# Boost_converter.net
KiCad netlist of a schematic drawn in Altium Designer
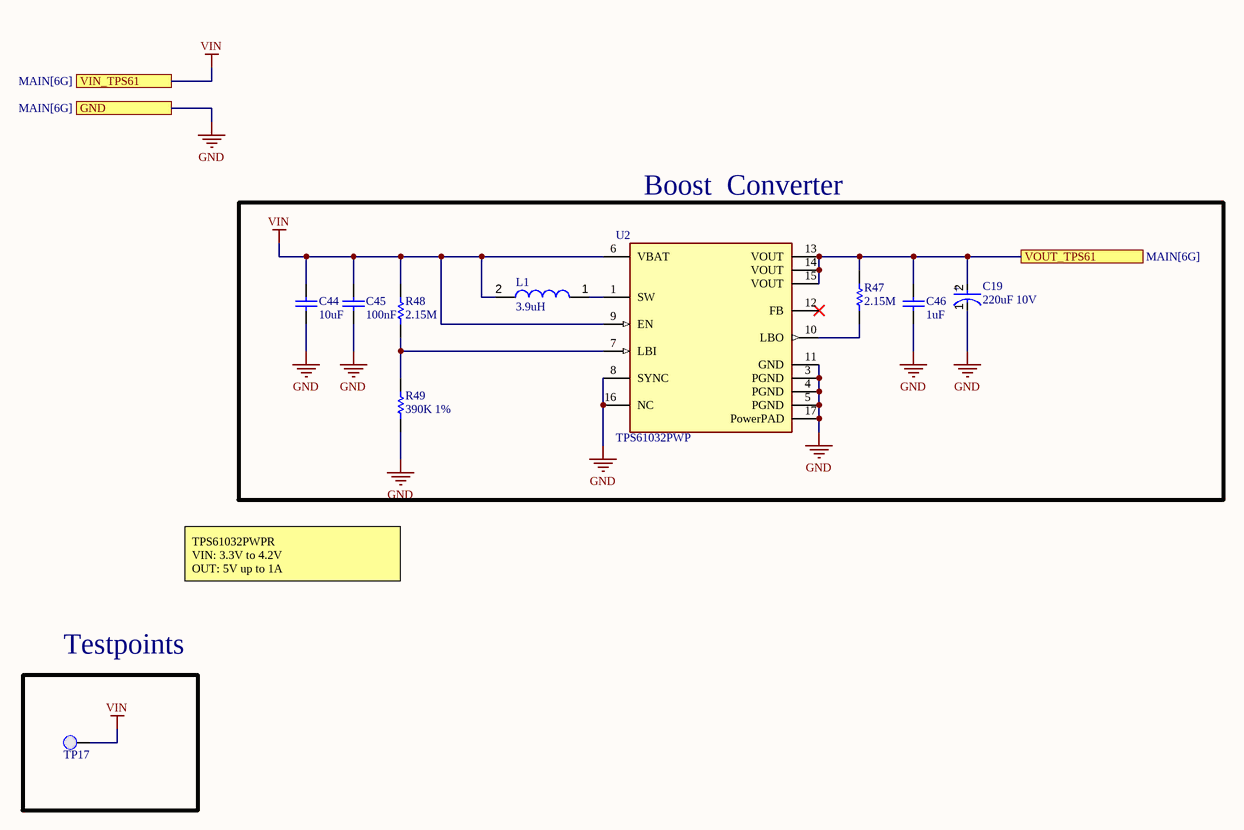
[diagram p0: Boost converter.SchDoc]

(export (version "E")
  (design (tool "Eeschema 10.0.6"))
  (components
    (comp (ref "C19")
      (value "220uF 10V")
      (footprint "FP-T495D227K010ATE100-MFG")
      (description "CAP TANT 220UF 10% 10V 2917, T495D227K010ATE100")
      (fields (field (name "TOLERANCE") "10%") (field (name "VOLTAGE") "10V"))
      (libsource (lib "Altium Content Vault") (part "203bc49f2ac43e59fd269a8c329ed05"))
    )
    (comp (ref "C44")
      (value "10uF")
      (footprint "CAPC2012X127N")
      (description "Boost Cin, Buck Cin-Cap Ceramic 10uF 16V X7R 20% SMD 0805 125°C Blister T/R")
      (fields (field (name "TOLERANCE") "20%") (field (name "MANUFACTURER") "Murata"))
      (libsource (lib "Schlib1") (part "CMP-06035-062410-1"))
    )
    (comp (ref "C45")
      (value "100nF")
      (footprint "CAPC1005X55X25LL05T10")
      (description "Boost Cinx, Cap 100NF 16V 0402 SMD 10% X7R")
      (fields
        (field (name "MANUFACTURER") "Murata")
        (field (name "MANUFACTURER PART NUMBER") "GRM155R71A104KA01D")
      )
      (libsource (lib "Schlib1") (part "CMP-2000-06331-1"))
    )
    (comp (ref "C46")
      (value "1uF")
      (footprint "CAPC1608X90")
      (description "Boost Coutx, Cap Ceramic 1uF 16V X7R 5% SMD 0603 125°C Paper T/R")
      (fields (field (name "MF") "{'manufacturer': u'KEMET'}") (field (name "MP") "C0603C105K8PACTU"))
      (libsource (lib "Schlib1") (part "C0603C105K8PACTU"))
    )
    (comp (ref "L1")
      (value "3.9uH")
      (footprint "7843330390")
      (description "Boost L1-Inductor, Aec-Q200, 3.9Uh, Shld, 11.2A Rohs Compliant: Yes")
      (fields
        (field (name "MANUFACTURER") "Wurth Electronics")
        (field (name "MANUFACTURER PART NUMBER") "7843330390")
      )
      (libsource (lib "Schlib1") (part "7843330390"))
    )
    (comp (ref "R47")
      (value "2.15M")
      (footprint "RESC1005X40X25ML05T05")
      (description "Boost Rlbt-Res Thick Film 0402 2.15M Ohm 1% 1/16W ±100ppm/°C Molded SMD SMD Paper T/R")
      (fields (field (name "MANUFACTURER") "Vishay Dale") (field (name "PART NUMBER") "CRCW04022M15FKED"))
      (libsource (lib "Schlib1") (part "CMP-2002-00322-1"))
    )
    (comp (ref "R48")
      (value "2.15M")
      (footprint "RESC1005X40X25ML05T05")
      (description "Boost Rlbt-Res Thick Film 0402 2.15M Ohm 1% 1/16W ±100ppm/°C Molded SMD SMD Paper T/R")
      (fields (field (name "MANUFACTURER") "Vishay Dale") (field (name "PART NUMBER") "CRCW04022M15FKED"))
      (libsource (lib "Schlib1") (part "CMP-2002-00322-1"))
    )
    (comp (ref "R49")
      (value "390K 1%")
      (footprint "RESC0603(1608)_M")
      (description "Boost Rlbb-Res Thick Film 0603 390K Ohm 1% 0.1W(1/10W) ±100ppm/C Pad SMD T/R")
      (fields (field (name "POWER") "0.1 W") (field (name "TOLERANCE") "1 %"))
      (libsource (lib "Schlib1") (part "CMP-1012-00802-1"))
    )
    (comp (ref "TP17")
      (value "0.1\" Pad")
      (footprint "PCBComponent")
      (libsource (lib "Components - 12.02.20 - 18.05") (part "0.1{dblquote} Pad-A.4"))
    )
    (comp (ref "U2")
      (value "TPS61032PWP")
      (footprint "FP-PWP0016C-MFG")
      (description "IC REG BOOST 5V 3.6A 16HTSSOP")
      (libsource (lib "Altium Content Vault") (part "1b52d660db08717e2baef4041dde2d0"))
    )
  )
  (nets
    (net (code "1") (name "/VOUT_TPS61") (class "Default")
      (node (ref "C19") (pin "2") (pinfunction "A_2") (pintype "passive"))
      (node (ref "C46") (pin "2") (pinfunction "2_2") (pintype "passive"))
      (node (ref "R47") (pin "2") (pinfunction "2_2") (pintype "passive"))
      (node (ref "U2") (pin "13") (pinfunction "VOUT_13") (pintype "power_in"))
      (node (ref "U2") (pin "14") (pinfunction "VOUT_14") (pintype "power_in"))
      (node (ref "U2") (pin "15") (pinfunction "VOUT_15") (pintype "power_in"))
    )
    (net (code "2") (name "GND") (class "Default")
      (node (ref "C19") (pin "1") (pinfunction "C_1") (pintype "passive"))
      (node (ref "C44") (pin "1") (pinfunction "1_1") (pintype "passive"))
      (node (ref "C45") (pin "1") (pinfunction "1_1") (pintype "passive"))
      (node (ref "C46") (pin "1") (pinfunction "1_1") (pintype "passive"))
      (node (ref "R49") (pin "1") (pinfunction "1_1") (pintype "passive"))
      (node (ref "U2") (pin "11") (pinfunction "GND_11") (pintype "power_in"))
      (node (ref "U2") (pin "16") (pinfunction "NC_16") (pintype "passive"))
      (node (ref "U2") (pin "17") (pinfunction "PowerPAD_17") (pintype "power_in"))
      (node (ref "U2") (pin "3") (pinfunction "PGND_3") (pintype "power_in"))
      (node (ref "U2") (pin "4") (pinfunction "PGND_4") (pintype "power_in"))
      (node (ref "U2") (pin "5") (pinfunction "PGND_5") (pintype "power_in"))
      (node (ref "U2") (pin "8") (pinfunction "SYNC_8") (pintype "passive"))
    )
    (net (code "3") (name "Net-(U2-LBI)") (class "Default")
      (node (ref "R48") (pin "1") (pinfunction "1_1") (pintype "passive"))
      (node (ref "R49") (pin "2") (pinfunction "2_2") (pintype "passive"))
      (node (ref "U2") (pin "7") (pinfunction "LBI_7") (pintype "input"))
    )
    (net (code "4") (name "Net-(U2-LBO)") (class "Default")
      (node (ref "R47") (pin "1") (pinfunction "1_1") (pintype "passive"))
      (node (ref "U2") (pin "10") (pinfunction "LBO_10") (pintype "output"))
    )
    (net (code "5") (name "Net-(U2-SW)") (class "Default")
      (node (ref "L1") (pin "1") (pinfunction "1_1") (pintype "passive"))
      (node (ref "U2") (pin "1") (pinfunction "SW_1") (pintype "passive"))
    )
    (net (code "6") (name "VIN") (class "Default")
      (node (ref "C44") (pin "2") (pinfunction "2_2") (pintype "passive"))
      (node (ref "C45") (pin "2") (pinfunction "2_2") (pintype "passive"))
      (node (ref "L1") (pin "2") (pinfunction "2_2") (pintype "passive"))
      (node (ref "R48") (pin "2") (pinfunction "2_2") (pintype "passive"))
      (node (ref "TP17") (pin "1") (pinfunction "PAD_1") (pintype "passive"))
      (node (ref "U2") (pin "6") (pinfunction "VBAT_6") (pintype "power_in"))
      (node (ref "U2") (pin "9") (pinfunction "EN_9") (pintype "input"))
    )
    (net (code "7") (name "unconnected-(U2-FB-Pad12)") (class "Default")
      (node (ref "U2") (pin "12") (pinfunction "FB_12") (pintype "passive+no_connect"))
    )
  )
)
